# Sheet1.net
KiCad netlist of a schematic drawn in Altium Designer
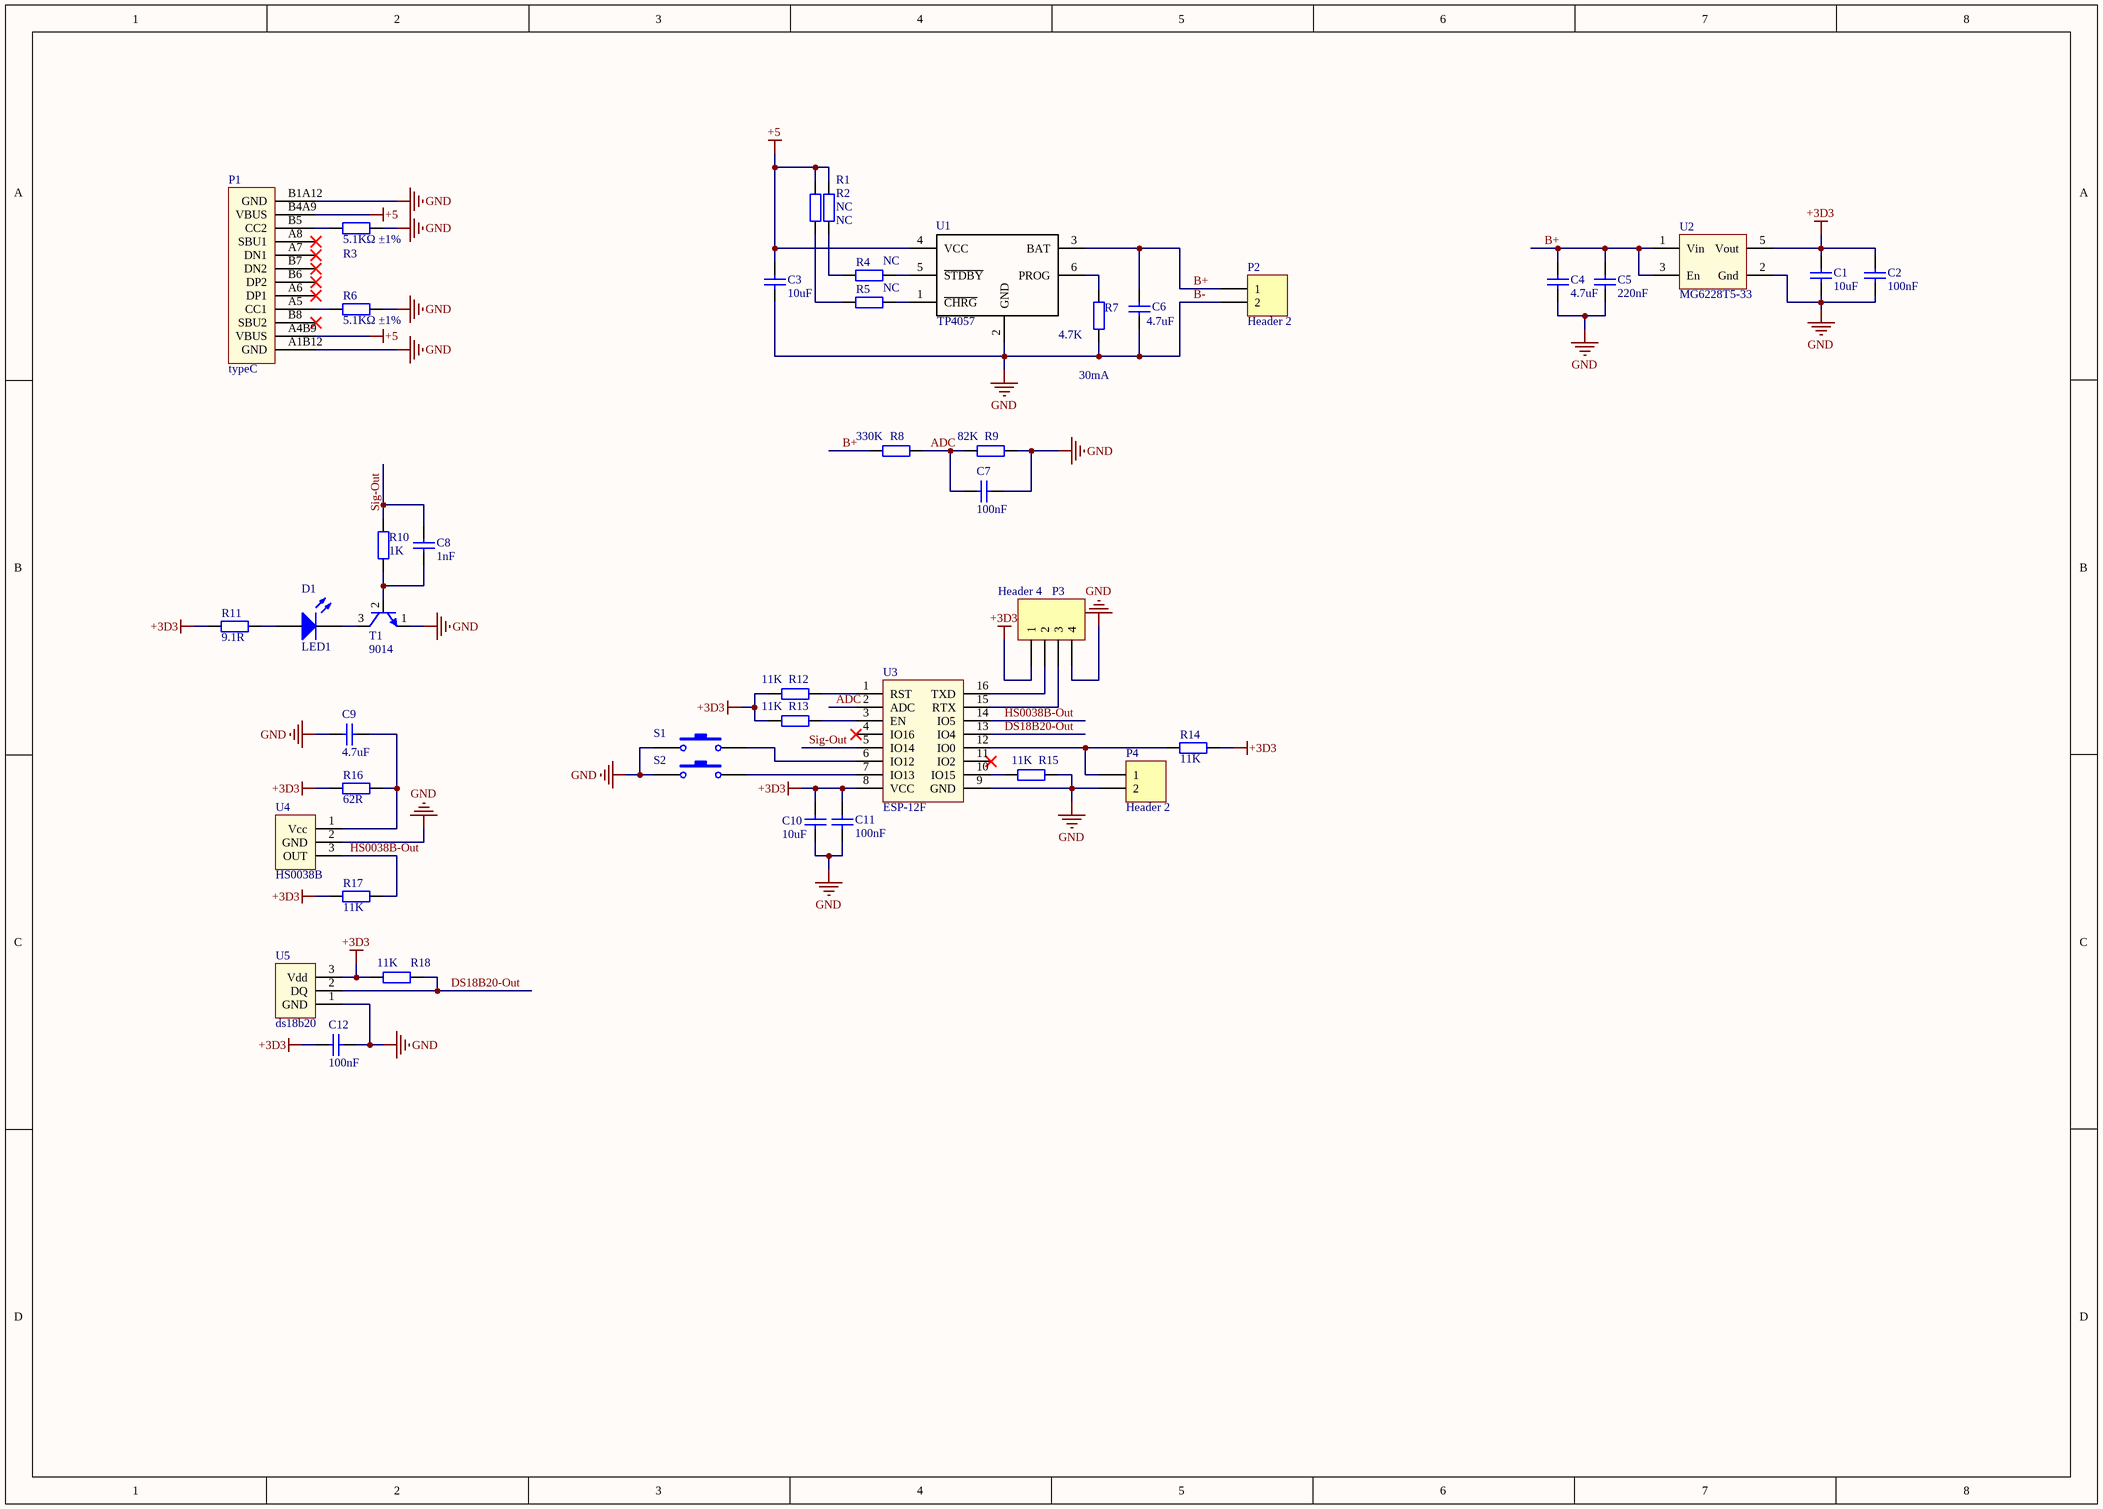
[diagram p0: Sheet1.SchDoc]

(export (version "E")
  (design (tool "Eeschema 10.0.6"))
  (components
    (comp (ref "C1")
      (value "10uF")
      (footprint "0603_C")
      (description "Chip capacitors")
      (fields
        (field (name "MANUFACTURER") "Samsung Electro-Mechanics")
        (field (name "PARTNUMBER") "CL10A106KP8NNNC")
      )
      (libsource (lib "Miscellaneous Devices LC") (part "0603 10uF (106) 10% 10V"))
    )
    (comp (ref "C2")
      (value "100nF")
      (footprint "0603_C")
      (description "Chip capacitors")
      (fields (field (name "MANUFACTURER") "YAGEO") (field (name "PARTNUMBER") "CC0603KRX7R9BB104"))
      (libsource (lib "Miscellaneous Devices LC") (part "0603 100nF (104) 10% 50V"))
    )
    (comp (ref "C3")
      (value "10uF")
      (footprint "0603_C")
      (description "Chip capacitors")
      (fields
        (field (name "MANUFACTURER") "Samsung Electro-Mechanics")
        (field (name "PARTNUMBER") "CL10A106KP8NNNC")
      )
      (libsource (lib "Miscellaneous Devices LC") (part "0603 10uF (106) 10% 10V"))
    )
    (comp (ref "C4")
      (value "4.7uF")
      (footprint "0603_C")
      (description "Chip capacitors")
      (fields
        (field (name "MANUFACTURER") "Samsung Electro-Mechanics")
        (field (name "PARTNUMBER") "CL10A475KO8NNNC")
      )
      (libsource (lib "Miscellaneous Devices LC") (part "0603 4.7uF (475) 10% 16V"))
    )
    (comp (ref "C5")
      (value "220nF")
      (footprint "0603_C")
      (description "Chip capacitors")
      (fields (field (name "MANUFACTURER") "YAGEO") (field (name "PARTNUMBER") "CC0603KRX7R9BB104"))
      (libsource (lib "Miscellaneous Devices LC") (part "0603 100nF (104) 10% 50V"))
    )
    (comp (ref "C6")
      (value "4.7uF")
      (footprint "0603_C")
      (description "Chip capacitors")
      (fields
        (field (name "MANUFACTURER") "Samsung Electro-Mechanics")
        (field (name "PARTNUMBER") "CL10A475KO8NNNC")
      )
      (libsource (lib "Miscellaneous Devices LC") (part "0603 4.7uF (475) 10% 16V"))
    )
    (comp (ref "C7")
      (value "100nF")
      (footprint "0603_C")
      (description "Chip capacitors")
      (fields (field (name "MANUFACTURER") "YAGEO") (field (name "PARTNUMBER") "CC0603KRX7R9BB104"))
      (libsource (lib "Miscellaneous Devices LC") (part "0603 100nF (104) 10% 50V"))
    )
    (comp (ref "C8")
      (value "1nF")
      (footprint "0603_C")
      (description "Chip capacitors")
      (fields
        (field (name "MANUFACTURER") "Samsung Electro-Mechanics")
        (field (name "PARTNUMBER") "CL10A106KP8NNNC")
      )
      (libsource (lib "Miscellaneous Devices LC") (part "0603 10uF (106) 10% 10V"))
    )
    (comp (ref "C9")
      (value "4.7uF")
      (footprint "0603_C")
      (description "Chip capacitors")
      (fields
        (field (name "MANUFACTURER") "Samsung Electro-Mechanics")
        (field (name "PARTNUMBER") "CL10A106KP8NNNC")
      )
      (libsource (lib "Miscellaneous Devices LC") (part "0603 10uF (106) 10% 10V"))
    )
    (comp (ref "C10")
      (value "10uF")
      (footprint "0603_C")
      (description "Chip capacitors")
      (fields
        (field (name "MANUFACTURER") "Samsung Electro-Mechanics")
        (field (name "PARTNUMBER") "CL10A106KP8NNNC")
      )
      (libsource (lib "Miscellaneous Devices LC") (part "0603 10uF (106) 10% 10V"))
    )
    (comp (ref "C11")
      (value "100nF")
      (footprint "0603_C")
      (description "Chip capacitors")
      (fields (field (name "MANUFACTURER") "YAGEO") (field (name "PARTNUMBER") "CC0603KRX7R9BB104"))
      (libsource (lib "Miscellaneous Devices LC") (part "0603 100nF (104) 10% 50V"))
    )
    (comp (ref "C12")
      (value "100nF")
      (footprint "0603_C")
      (description "Chip capacitors")
      (fields
        (field (name "MANUFACTURER") "Samsung Electro-Mechanics")
        (field (name "PARTNUMBER") "CL10A106KP8NNNC")
      )
      (libsource (lib "Miscellaneous Devices LC") (part "0603 10uF (106) 10% 10V"))
    )
    (comp (ref "D1")
      (value "LED1")
      (footprint "LED-1")
      (description "Typical RED GaAs LED")
      (fields (field (name "PUBLISHER") "Altium Limited"))
      (libsource (lib "Miscellaneous Devices") (part "LED1"))
    )
    (comp (ref "P1") (value "typeC") (footprint "USB_C_M") (libsource (lib "myschlib") (part "typeC")))
    (comp (ref "P2")
      (value "Header 2")
      (footprint "CR2450")
      (description "Header, 2-Pin")
      (libsource (lib "Miscellaneous Connectors") (part "Header 2"))
    )
    (comp (ref "P3")
      (value "Header 4")
      (footprint "HDR1X4")
      (description "Header, 4-Pin")
      (fields (field (name "PUBLISHER") "Altium Limited"))
      (libsource (lib "Miscellaneous Connectors") (part "Header 4"))
    )
    (comp (ref "P4")
      (value "Header 2")
      (footprint "HDR1X2")
      (description "Header, 2-Pin")
      (fields (field (name "PUBLISHER") "Altium Limited"))
      (libsource (lib "Miscellaneous Connectors") (part "Header 2"))
    )
    (comp (ref "R1")
      (value "NC")
      (footprint "0603_R")
      (description "Chip resistor")
      (fields (field (name "MANUFACTURER") "Uniroyal Elec") (field (name "PARTNUMBER") "0603WAF1002T5E"))
      (libsource (lib "Miscellaneous Devices LC") (part "0603 10K (1002) 1%"))
    )
    (comp (ref "R2")
      (value "NC")
      (footprint "0603_R")
      (description "Chip resistor")
      (fields (field (name "MANUFACTURER") "Uniroyal Elec") (field (name "PARTNUMBER") "0603WAF1002T5E"))
      (libsource (lib "Miscellaneous Devices LC") (part "0603 10K (1002) 1%"))
    )
    (comp (ref "R3")
      (value "5.1KΩ ±1%")
      (footprint "0603_R")
      (description "Chip resistor")
      (fields (field (name "MANUFACTURER") "Uniroyal Elec") (field (name "PARTNUMBER") "0603WAF2401T5E"))
      (libsource (lib "") (part "0603 2.4K (2401) 1%_1"))
    )
    (comp (ref "R4")
      (value "NC")
      (footprint "0603_R")
      (description "Chip resistor")
      (fields (field (name "MANUFACTURER") "Uniroyal Elec") (field (name "PARTNUMBER") "0603WAF1002T5E"))
      (libsource (lib "") (part "0603 10K (1002) 1%_1"))
    )
    (comp (ref "R5")
      (value "NC")
      (footprint "0603_R")
      (description "Chip resistor")
      (fields (field (name "MANUFACTURER") "Uniroyal Elec") (field (name "PARTNUMBER") "0603WAF1002T5E"))
      (libsource (lib "") (part "0603 10K (1002) 1%_2"))
    )
    (comp (ref "R6")
      (value "5.1KΩ ±1%")
      (footprint "0603_R")
      (description "Chip resistor")
      (fields (field (name "MANUFACTURER") "Uniroyal Elec") (field (name "PARTNUMBER") "0603WAF2401T5E"))
      (libsource (lib "") (part "0603 2.4K (2401) 1%_1"))
    )
    (comp (ref "R7")
      (value "4.7K")
      (footprint "0603_R")
      (description "Chip resistor")
      (fields (field (name "MANUFACTURER") "Uniroyal Elec") (field (name "PARTNUMBER") "0603WAF2401T5E"))
      (libsource (lib "") (part "0603 2.4K (2401) 1%_2"))
    )
    (comp (ref "R8")
      (value "330K")
      (footprint "0603_R")
      (description "Chip resistor")
      (fields (field (name "MANUFACTURER") "Uniroyal Elec") (field (name "PARTNUMBER") "0603WAF2401T5E"))
      (libsource (lib "Miscellaneous Devices LC") (part "0603 2.4K (2401) 1%"))
    )
    (comp (ref "R9")
      (value "82K")
      (footprint "0603_R")
      (description "Chip resistor")
      (fields (field (name "MANUFACTURER") "Uniroyal Elec") (field (name "PARTNUMBER") "0603WAF2401T5E"))
      (libsource (lib "Miscellaneous Devices LC") (part "0603 2.4K (2401) 1%"))
    )
    (comp (ref "R10")
      (value "1K")
      (footprint "0603_R")
      (description "Chip resistor")
      (fields (field (name "MANUFACTURER") "Uniroyal Elec") (field (name "PARTNUMBER") "0603WAF2401T5E"))
      (libsource (lib "") (part "0603 2.4K (2401) 1%_2"))
    )
    (comp (ref "R11")
      (value "9.1R")
      (footprint "0603_R")
      (description "Chip resistor")
      (fields (field (name "MANUFACTURER") "Uniroyal Elec") (field (name "PARTNUMBER") "0603WAF2401T5E"))
      (libsource (lib "Miscellaneous Devices LC") (part "0603 2.4K (2401) 1%"))
    )
    (comp (ref "R12")
      (value "11K")
      (footprint "0603_R")
      (description "Chip resistor")
      (fields (field (name "MANUFACTURER") "Uniroyal Elec") (field (name "PARTNUMBER") "0603WAF2401T5E"))
      (libsource (lib "Miscellaneous Devices LC") (part "0603 2.4K (2401) 1%"))
    )
    (comp (ref "R13")
      (value "11K")
      (footprint "0603_R")
      (description "Chip resistor")
      (fields (field (name "MANUFACTURER") "Uniroyal Elec") (field (name "PARTNUMBER") "0603WAF2401T5E"))
      (libsource (lib "Miscellaneous Devices LC") (part "0603 2.4K (2401) 1%"))
    )
    (comp (ref "R14")
      (value "11K")
      (footprint "0603_R")
      (description "Chip resistor")
      (fields (field (name "MANUFACTURER") "Uniroyal Elec") (field (name "PARTNUMBER") "0603WAF2401T5E"))
      (libsource (lib "") (part "0603 2.4K (2401) 1%_1"))
    )
    (comp (ref "R15")
      (value "11K")
      (footprint "0603_R")
      (description "Chip resistor")
      (fields (field (name "MANUFACTURER") "Uniroyal Elec") (field (name "PARTNUMBER") "0603WAF2401T5E"))
      (libsource (lib "") (part "0603 2.4K (2401) 1%_1"))
    )
    (comp (ref "R16")
      (value "62R")
      (footprint "0603_R")
      (description "Chip resistor")
      (fields (field (name "MANUFACTURER") "Uniroyal Elec") (field (name "PARTNUMBER") "0603WAF2401T5E"))
      (libsource (lib "") (part "0603 2.4K (2401) 1%_1"))
    )
    (comp (ref "R17")
      (value "11K")
      (footprint "0603_R")
      (description "Chip resistor")
      (fields (field (name "MANUFACTURER") "Uniroyal Elec") (field (name "PARTNUMBER") "0603WAF2401T5E"))
      (libsource (lib "") (part "0603 2.4K (2401) 1%_1"))
    )
    (comp (ref "R18")
      (value "11K")
      (footprint "0603_R")
      (description "Chip resistor")
      (fields (field (name "MANUFACTURER") "Uniroyal Elec") (field (name "PARTNUMBER") "0603WAF2401T5E"))
      (libsource (lib "") (part "0603 2.4K (2401) 1%_1"))
    )
    (comp (ref "S1")
      (value "SW-PB")
      (footprint "6x6-key")
      (description "Switch")
      (fields (field (name "PUBLISHER") "Altium Limited"))
      (libsource (lib "Miscellaneous Devices") (part "SW-PB"))
    )
    (comp (ref "S2")
      (value "SW-PB")
      (footprint "6x6-key")
      (description "Switch")
      (fields (field (name "PUBLISHER") "Altium Limited"))
      (libsource (lib "Miscellaneous Devices") (part "SW-PB"))
    )
    (comp (ref "T1") (value "9014") (footprint "TO-92") (libsource (lib "KongTiaoT") (part "9014")))
    (comp (ref "U1")
      (value "TP4057")
      (footprint "SOT-23-6")
      (libsource (lib "ZJYM130-CH1115") (part "TP4057"))
    )
    (comp (ref "U2")
      (value "MG6228T5-33")
      (footprint "SOT-23-5")
      (libsource (lib "KongTiaoT") (part "MG6228T5-33"))
    )
    (comp (ref "U3")
      (value "ESP-12F")
      (footprint "ESP-12F-16Pin")
      (libsource (lib "KongTiaoT") (part "ESP-12F"))
    )
    (comp (ref "U4") (value "HS0038B") (footprint "HS0038B") (libsource (lib "KongTiaoT") (part "HS0038B")))
    (comp (ref "U5") (value "ds18b20") (footprint "TO-92") (libsource (lib "KongTiaoT") (part "ds18b20")))
  )
  (nets
    (net (code "1") (name "+3D3") (class "Default")
      (node (ref "C1") (pin "2") (pinfunction "2_2") (pintype "passive"))
      (node (ref "C10") (pin "2") (pinfunction "2_2") (pintype "passive"))
      (node (ref "C11") (pin "2") (pinfunction "2_2") (pintype "passive"))
      (node (ref "C12") (pin "2") (pinfunction "2_2") (pintype "passive"))
      (node (ref "C2") (pin "2") (pinfunction "2_2") (pintype "passive"))
      (node (ref "P3") (pin "1") (pinfunction "1_1") (pintype "passive"))
      (node (ref "R11") (pin "1") (pinfunction "1_1") (pintype "passive"))
      (node (ref "R12") (pin "1") (pinfunction "1_1") (pintype "passive"))
      (node (ref "R13") (pin "1") (pinfunction "1_1") (pintype "passive"))
      (node (ref "R14") (pin "1") (pinfunction "1_1") (pintype "passive"))
      (node (ref "R16") (pin "2") (pinfunction "2_2") (pintype "passive"))
      (node (ref "R17") (pin "2") (pinfunction "2_2") (pintype "passive"))
      (node (ref "R18") (pin "2") (pinfunction "2_2") (pintype "passive"))
      (node (ref "U2") (pin "5") (pinfunction "Vout_5") (pintype "passive"))
      (node (ref "U3") (pin "8") (pinfunction "VCC_8") (pintype "passive"))
      (node (ref "U5") (pin "3") (pinfunction "Vdd_3") (pintype "passive"))
    )
    (net (code "2") (name "+5") (class "Default")
      (node (ref "C3") (pin "2") (pinfunction "2_2") (pintype "passive"))
      (node (ref "P1") (pin "A4B9") (pinfunction "VBUS_A4B9") (pintype "passive"))
      (node (ref "P1") (pin "B4A9") (pinfunction "VBUS_B4A9") (pintype "passive"))
      (node (ref "R1") (pin "2") (pinfunction "2_2") (pintype "passive"))
      (node (ref "R2") (pin "2") (pinfunction "2_2") (pintype "passive"))
      (node (ref "U1") (pin "4") (pinfunction "VCC_4") (pintype "passive"))
    )
    (net (code "3") (name "/ADC") (class "Default")
      (node (ref "C7") (pin "2") (pinfunction "2_2") (pintype "passive"))
      (node (ref "R8") (pin "2") (pinfunction "2_2") (pintype "passive"))
      (node (ref "R9") (pin "1") (pinfunction "1_1") (pintype "passive"))
      (node (ref "U3") (pin "2") (pinfunction "ADC_2") (pintype "passive"))
    )
    (net (code "4") (name "/B+") (class "Default")
      (node (ref "C4") (pin "2") (pinfunction "2_2") (pintype "passive"))
      (node (ref "C5") (pin "2") (pinfunction "2_2") (pintype "passive"))
      (node (ref "C6") (pin "2") (pinfunction "2_2") (pintype "passive"))
      (node (ref "P2") (pin "1") (pinfunction "1_1") (pintype "passive"))
      (node (ref "R8") (pin "1") (pinfunction "1_1") (pintype "passive"))
      (node (ref "U1") (pin "3") (pinfunction "BAT_3") (pintype "passive"))
      (node (ref "U2") (pin "1") (pinfunction "Vin_1") (pintype "passive"))
      (node (ref "U2") (pin "3") (pinfunction "En_3") (pintype "passive"))
    )
    (net (code "5") (name "/DS18B20-Out") (class "Default")
      (node (ref "R18") (pin "1") (pinfunction "1_1") (pintype "passive"))
      (node (ref "U3") (pin "13") (pinfunction "IO4_13") (pintype "passive"))
      (node (ref "U5") (pin "2") (pinfunction "DQ_2") (pintype "passive"))
    )
    (net (code "6") (name "/HS0038B-Out") (class "Default")
      (node (ref "R17") (pin "1") (pinfunction "1_1") (pintype "passive"))
      (node (ref "U3") (pin "14") (pinfunction "IO5_14") (pintype "passive"))
      (node (ref "U4") (pin "3") (pinfunction "OUT_3") (pintype "passive"))
    )
    (net (code "7") (name "/Sig-Out") (class "Default")
      (node (ref "C8") (pin "1") (pinfunction "1_1") (pintype "passive"))
      (node (ref "R10") (pin "2") (pinfunction "2_2") (pintype "passive"))
      (node (ref "U3") (pin "5") (pinfunction "IO14_5") (pintype "passive"))
    )
    (net (code "8") (name "GND") (class "Default")
      (node (ref "C1") (pin "1") (pinfunction "1_1") (pintype "passive"))
      (node (ref "C10") (pin "1") (pinfunction "1_1") (pintype "passive"))
      (node (ref "C11") (pin "1") (pinfunction "1_1") (pintype "passive"))
      (node (ref "C12") (pin "1") (pinfunction "1_1") (pintype "passive"))
      (node (ref "C2") (pin "1") (pinfunction "1_1") (pintype "passive"))
      (node (ref "C3") (pin "1") (pinfunction "1_1") (pintype "passive"))
      (node (ref "C4") (pin "1") (pinfunction "1_1") (pintype "passive"))
      (node (ref "C5") (pin "1") (pinfunction "1_1") (pintype "passive"))
      (node (ref "C6") (pin "1") (pinfunction "1_1") (pintype "passive"))
      (node (ref "C7") (pin "1") (pinfunction "1_1") (pintype "passive"))
      (node (ref "C9") (pin "2") (pinfunction "2_2") (pintype "passive"))
      (node (ref "P1") (pin "A1B12") (pinfunction "GND_A1B12") (pintype "passive"))
      (node (ref "P1") (pin "B1A12") (pinfunction "GND_B1A12") (pintype "passive"))
      (node (ref "P2") (pin "2") (pinfunction "2_2") (pintype "passive"))
      (node (ref "P3") (pin "4") (pinfunction "4_4") (pintype "passive"))
      (node (ref "P4") (pin "2") (pinfunction "2_2") (pintype "passive"))
      (node (ref "R15") (pin "1") (pinfunction "1_1") (pintype "passive"))
      (node (ref "R3") (pin "1") (pinfunction "1_1") (pintype "passive"))
      (node (ref "R6") (pin "1") (pinfunction "1_1") (pintype "passive"))
      (node (ref "R7") (pin "1") (pinfunction "1_1") (pintype "passive"))
      (node (ref "R9") (pin "2") (pinfunction "2_2") (pintype "passive"))
      (node (ref "S1") (pin "1") (pinfunction "1_1") (pintype "passive"))
      (node (ref "S2") (pin "1") (pinfunction "1_1") (pintype "passive"))
      (node (ref "T1") (pin "1") (pinfunction "E_1") (pintype "passive"))
      (node (ref "U1") (pin "2") (pinfunction "GND_2") (pintype "passive"))
      (node (ref "U2") (pin "2") (pinfunction "Gnd_2") (pintype "passive"))
      (node (ref "U3") (pin "9") (pinfunction "GND_9") (pintype "passive"))
      (node (ref "U4") (pin "2") (pinfunction "GND_2") (pintype "passive"))
      (node (ref "U5") (pin "1") (pinfunction "GND_1") (pintype "passive"))
    )
    (net (code "9") (name "Net-(D1-A)") (class "Default")
      (node (ref "D1") (pin "1") (pinfunction "A_1") (pintype "passive"))
      (node (ref "R11") (pin "2") (pinfunction "2_2") (pintype "passive"))
    )
    (net (code "10") (name "Net-(D1-K)") (class "Default")
      (node (ref "D1") (pin "2") (pinfunction "K_2") (pintype "passive"))
      (node (ref "T1") (pin "3") (pinfunction "C_3") (pintype "passive"))
    )
    (net (code "11") (name "Net-(P1-CC1)") (class "Default")
      (node (ref "P1") (pin "A5") (pinfunction "CC1_A5") (pintype "passive"))
      (node (ref "R6") (pin "2") (pinfunction "2_2") (pintype "passive"))
    )
    (net (code "12") (name "Net-(P1-CC2)") (class "Default")
      (node (ref "P1") (pin "B5") (pinfunction "CC2_B5") (pintype "passive"))
      (node (ref "R3") (pin "2") (pinfunction "2_2") (pintype "passive"))
    )
    (net (code "13") (name "Net-(R1-Pad1)") (class "Default")
      (node (ref "R1") (pin "1") (pinfunction "1_1") (pintype "passive"))
      (node (ref "R5") (pin "2") (pinfunction "2_2") (pintype "passive"))
    )
    (net (code "14") (name "Net-(R2-Pad1)") (class "Default")
      (node (ref "R2") (pin "1") (pinfunction "1_1") (pintype "passive"))
      (node (ref "R4") (pin "1") (pinfunction "1_1") (pintype "passive"))
    )
    (net (code "15") (name "Net-(T1-B)") (class "Default")
      (node (ref "C8") (pin "2") (pinfunction "2_2") (pintype "passive"))
      (node (ref "R10") (pin "1") (pinfunction "1_1") (pintype "passive"))
      (node (ref "T1") (pin "2") (pinfunction "B_2") (pintype "passive"))
    )
    (net (code "16") (name "Net-(U1-PROG)") (class "Default")
      (node (ref "R7") (pin "2") (pinfunction "2_2") (pintype "passive"))
      (node (ref "U1") (pin "6") (pinfunction "PROG_6") (pintype "passive"))
    )
    (net (code "17") (name "Net-(U1-~{CHRG})") (class "Default")
      (node (ref "R5") (pin "1") (pinfunction "1_1") (pintype "passive"))
      (node (ref "U1") (pin "1") (pinfunction "~{CHRG}_1") (pintype "passive"))
    )
    (net (code "18") (name "Net-(U1-~{STDBY})") (class "Default")
      (node (ref "R4") (pin "2") (pinfunction "2_2") (pintype "passive"))
      (node (ref "U1") (pin "5") (pinfunction "~{STDBY}_5") (pintype "passive"))
    )
    (net (code "19") (name "Net-(U3-EN)") (class "Default")
      (node (ref "R13") (pin "2") (pinfunction "2_2") (pintype "passive"))
      (node (ref "U3") (pin "3") (pinfunction "EN_3") (pintype "passive"))
    )
    (net (code "20") (name "Net-(U3-IO0)") (class "Default")
      (node (ref "P4") (pin "1") (pinfunction "1_1") (pintype "passive"))
      (node (ref "R14") (pin "2") (pinfunction "2_2") (pintype "passive"))
      (node (ref "U3") (pin "12") (pinfunction "IO0_12") (pintype "passive"))
    )
    (net (code "21") (name "Net-(U3-IO12)") (class "Default")
      (node (ref "S1") (pin "2") (pinfunction "2_2") (pintype "passive"))
      (node (ref "U3") (pin "6") (pinfunction "IO12_6") (pintype "passive"))
    )
    (net (code "22") (name "Net-(U3-IO13)") (class "Default")
      (node (ref "S2") (pin "2") (pinfunction "2_2") (pintype "passive"))
      (node (ref "U3") (pin "7") (pinfunction "IO13_7") (pintype "passive"))
    )
    (net (code "23") (name "Net-(U3-IO15)") (class "Default")
      (node (ref "R15") (pin "2") (pinfunction "2_2") (pintype "passive"))
      (node (ref "U3") (pin "10") (pinfunction "IO15_10") (pintype "passive"))
    )
    (net (code "24") (name "Net-(U3-RST)") (class "Default")
      (node (ref "R12") (pin "2") (pinfunction "2_2") (pintype "passive"))
      (node (ref "U3") (pin "1") (pinfunction "RST_1") (pintype "passive"))
    )
    (net (code "25") (name "Net-(U3-RTX)") (class "Default")
      (node (ref "P3") (pin "3") (pinfunction "3_3") (pintype "passive"))
      (node (ref "U3") (pin "15") (pinfunction "RTX_15") (pintype "passive"))
    )
    (net (code "26") (name "Net-(U3-TXD)") (class "Default")
      (node (ref "P3") (pin "2") (pinfunction "2_2") (pintype "passive"))
      (node (ref "U3") (pin "16") (pinfunction "TXD_16") (pintype "passive"))
    )
    (net (code "27") (name "Net-(U4-Vcc)") (class "Default")
      (node (ref "C9") (pin "1") (pinfunction "1_1") (pintype "passive"))
      (node (ref "R16") (pin "1") (pinfunction "1_1") (pintype "passive"))
      (node (ref "U4") (pin "1") (pinfunction "Vcc_1") (pintype "passive"))
    )
    (net (code "28") (name "unconnected-(P1-DN1-PadA7)") (class "Default")
      (node (ref "P1") (pin "A7") (pinfunction "DN1_A7") (pintype "passive+no_connect"))
    )
    (net (code "29") (name "unconnected-(P1-DN2-PadB7)") (class "Default")
      (node (ref "P1") (pin "B7") (pinfunction "DN2_B7") (pintype "passive+no_connect"))
    )
    (net (code "30") (name "unconnected-(P1-DP1-PadA6)") (class "Default")
      (node (ref "P1") (pin "A6") (pinfunction "DP1_A6") (pintype "passive+no_connect"))
    )
    (net (code "31") (name "unconnected-(P1-DP2-PadB6)") (class "Default")
      (node (ref "P1") (pin "B6") (pinfunction "DP2_B6") (pintype "passive+no_connect"))
    )
    (net (code "32") (name "unconnected-(P1-SBU1-PadA8)") (class "Default")
      (node (ref "P1") (pin "A8") (pinfunction "SBU1_A8") (pintype "passive+no_connect"))
    )
    (net (code "33") (name "unconnected-(P1-SBU2-PadB8)") (class "Default")
      (node (ref "P1") (pin "B8") (pinfunction "SBU2_B8") (pintype "passive+no_connect"))
    )
    (net (code "34") (name "unconnected-(U3-IO2-Pad11)") (class "Default")
      (node (ref "U3") (pin "11") (pinfunction "IO2_11") (pintype "passive+no_connect"))
    )
    (net (code "35") (name "unconnected-(U3-IO16-Pad4)") (class "Default")
      (node (ref "U3") (pin "4") (pinfunction "IO16_4") (pintype "passive+no_connect"))
    )
  )
)
